# power-hat.net
KiCad netlist of a schematic drawn in EAGLE
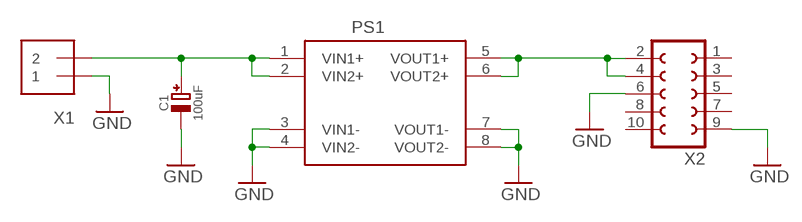
[diagram p0: schematic, sheet 1]

(export (version "E")
  (design (tool "Eeschema 10.0.6"))
  (components
    (comp (ref "C1")
      (value "100uF")
      (footprint "eagle-import:CELEC_3.5MM_8MM")
      (libsource (lib "eagle-import") (part "CAP_ELECTROLYTICPTH_3.5MMGRID_8MMDIA"))
    )
    (comp (ref "PS1")
      (value "K8801MODULE")
      (footprint "eagle-import:K8801")
      (libsource (lib "eagle-import") (part "K8801MODULE"))
    )
    (comp (ref "X1")
      (value "WR_TBL_1X2-3.5MM")
      (footprint "eagle-import:WR-TBL-1X2-3.5MM")
      (libsource (lib "eagle-import") (part "WR_TBL_1X2-3.5MM"))
    )
    (comp (ref "X2")
      (value "FE05-2")
      (footprint "eagle-import:FE05-2")
      (libsource (lib "eagle-import") (part "FE05-2"))
    )
  )
  (nets
    (net (code "1") (name "GND") (class "Default")
      (node (ref "C1") (pin "-") (pinfunction "-_-") (pintype "passive"))
      (node (ref "PS1") (pin "3") (pinfunction "VIN1-_3") (pintype "bidirectional"))
      (node (ref "PS1") (pin "4") (pinfunction "VIN2-_4") (pintype "bidirectional"))
      (node (ref "PS1") (pin "7") (pinfunction "VOUT1-_7") (pintype "bidirectional"))
      (node (ref "PS1") (pin "8") (pinfunction "VOUT2-_8") (pintype "bidirectional"))
      (node (ref "X1") (pin "1") (pinfunction "1_1") (pintype "passive"))
      (node (ref "X2") (pin "6") (pinfunction "6_6") (pintype "passive"))
      (node (ref "X2") (pin "9") (pinfunction "9_9") (pintype "passive"))
    )
    (net (code "2") (name "Net-(PS1-VIN1+)") (class "Default")
      (node (ref "C1") (pin "+") (pinfunction "+_+") (pintype "passive"))
      (node (ref "PS1") (pin "1") (pinfunction "VIN1+_1") (pintype "bidirectional"))
      (node (ref "PS1") (pin "2") (pinfunction "VIN2+_2") (pintype "bidirectional"))
      (node (ref "X1") (pin "2") (pinfunction "2_2") (pintype "passive"))
    )
    (net (code "3") (name "Net-(PS1-VOUT1+)") (class "Default")
      (node (ref "PS1") (pin "5") (pinfunction "VOUT1+_5") (pintype "bidirectional"))
      (node (ref "PS1") (pin "6") (pinfunction "VOUT2+_6") (pintype "bidirectional"))
      (node (ref "X2") (pin "2") (pinfunction "2_2") (pintype "passive"))
      (node (ref "X2") (pin "4") (pinfunction "4_4") (pintype "passive"))
    )
    (net (code "4") (name "unconnected-(X2-Pad1)") (class "Default")
      (node (ref "X2") (pin "1") (pinfunction "1_1") (pintype "passive"))
    )
    (net (code "5") (name "unconnected-(X2-Pad3)") (class "Default")
      (node (ref "X2") (pin "3") (pinfunction "3_3") (pintype "passive"))
    )
    (net (code "6") (name "unconnected-(X2-Pad5)") (class "Default")
      (node (ref "X2") (pin "5") (pinfunction "5_5") (pintype "passive"))
    )
    (net (code "7") (name "unconnected-(X2-Pad7)") (class "Default")
      (node (ref "X2") (pin "7") (pinfunction "7_7") (pintype "passive"))
    )
    (net (code "8") (name "unconnected-(X2-Pad8)") (class "Default")
      (node (ref "X2") (pin "8") (pinfunction "8_8") (pintype "passive"))
    )
    (net (code "9") (name "unconnected-(X2-Pad10)") (class "Default")
      (node (ref "X2") (pin "10") (pinfunction "10_10") (pintype "passive"))
    )
  )
)
